# blockDiagram.net
KiCad netlist of a schematic drawn in EAGLE
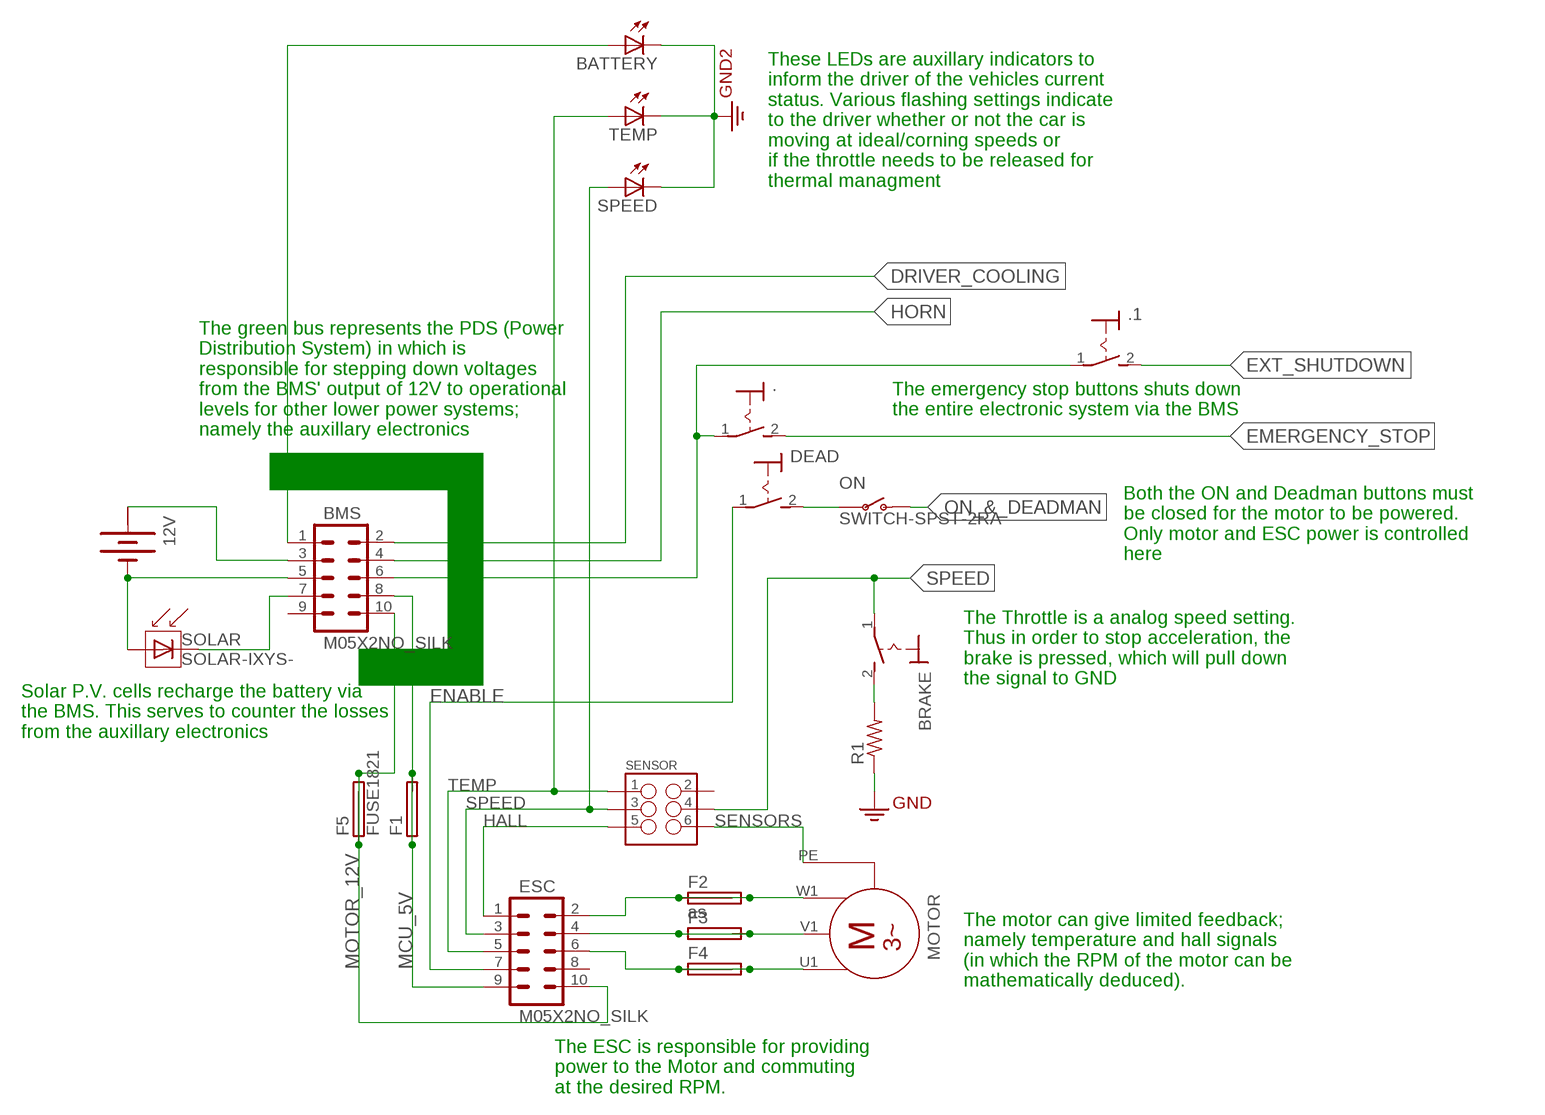
[diagram p0: schematic, sheet 1]

(export (version "E")
  (design (tool "Eeschema 10.0.6"))
  (components
    (comp (ref ".")
      (value "MS243")
      (footprint "eagle-import:MS243")
      (libsource (lib "eagle-import") (part "MS243"))
    )
    (comp (ref ".1")
      (value "MS243")
      (footprint "eagle-import:MS243")
      (libsource (lib "eagle-import") (part "MS243"))
    )
    (comp (ref "12V")
      (value "BATTERY")
      (footprint "eagle-import:BATTERY")
      (libsource (lib "eagle-import") (part "BATTERY"))
    )
    (comp (ref "BATTERY")
      (value "LED1206")
      (footprint "eagle-import:LED-1206")
      (libsource (lib "eagle-import") (part "LED1206"))
    )
    (comp (ref "BMS")
      (value "M05X2NO_SILK")
      (footprint "eagle-import:2X5_NOSILK")
      (libsource (lib "eagle-import") (part "M05X2NO_SILK"))
    )
    (comp (ref "BRAKE")
      (value "MS243")
      (footprint "eagle-import:MS243")
      (libsource (lib "eagle-import") (part "MS243"))
    )
    (comp (ref "DEAD")
      (value "MS243")
      (footprint "eagle-import:MS243")
      (libsource (lib "eagle-import") (part "MS243"))
    )
    (comp (ref "ESC")
      (value "M05X2NO_SILK")
      (footprint "eagle-import:2X5_NOSILK")
      (libsource (lib "eagle-import") (part "M05X2NO_SILK"))
    )
    (comp (ref "F1")
      (value "KS9V")
      (footprint "eagle-import:KS9V")
      (libsource (lib "eagle-import") (part "KS9V"))
    )
    (comp (ref "F2")
      (value "as")
      (footprint "eagle-import:KS9V")
      (libsource (lib "eagle-import") (part "KS9V"))
    )
    (comp (ref "F3")
      (value "KS9V")
      (footprint "eagle-import:KS9V")
      (libsource (lib "eagle-import") (part "KS9V"))
    )
    (comp (ref "F4")
      (value "KS9V")
      (footprint "eagle-import:KS9V")
      (libsource (lib "eagle-import") (part "KS9V"))
    )
    (comp (ref "F5")
      (value "FUSE1821")
      (footprint "eagle-import:FUSE_HOLDER_MENTOR-1821")
      (libsource (lib "eagle-import") (part "FUSE1821"))
    )
    (comp (ref "MOTOR")
      (value "MOTOR_3-POL_PE")
      (footprint "eagle-import:MOTOR_3-POL_PE")
      (libsource (lib "eagle-import") (part "MOTOR_3-POL_PE"))
    )
    (comp (ref "ON")
      (value "SWITCH-SPST-2RA")
      (footprint "eagle-import:R_SW_TH")
      (libsource (lib "eagle-import") (part "SWITCH-SPST-2RA"))
    )
    (comp (ref "R1")
      (value "R-US_0204/2V")
      (footprint "eagle-import:0204V")
      (libsource (lib "eagle-import") (part "R-US_0204/2V"))
    )
    (comp (ref "SENSOR")
      (value "M03X2")
      (footprint "eagle-import:2X3_SMD")
      (libsource (lib "eagle-import") (part "M03X2"))
    )
    (comp (ref "SOLAR")
      (value "SOLAR-IXYS-")
      (footprint "eagle-import:SOLARBIT-12X1")
      (libsource (lib "eagle-import") (part "SOLAR-IXYS-"))
    )
    (comp (ref "SPEED")
      (value "LED1206")
      (footprint "eagle-import:LED-1206")
      (libsource (lib "eagle-import") (part "LED1206"))
    )
    (comp (ref "TEMP")
      (value "LED1206")
      (footprint "eagle-import:LED-1206")
      (libsource (lib "eagle-import") (part "LED1206"))
    )
  )
  (nets
    (net (code "1") (name "/+") (class "Default")
      (node (ref "12V") (pin "+@1") (pinfunction "+_+@1") (pintype "power_in"))
    )
    (net (code "2") (name "/ENABLE") (class "Default")
      (node (ref "DEAD") (pin "1") (pinfunction "P_1") (pintype "passive"))
      (node (ref "ESC") (pin "7") (pinfunction "7_7") (pintype "passive"))
    )
    (net (code "3") (name "/HALL") (class "Default")
      (node (ref "ESC") (pin "1") (pinfunction "1_1") (pintype "passive"))
      (node (ref "SENSOR") (pin "5") (pinfunction "5_5") (pintype "bidirectional"))
    )
    (net (code "4") (name "/MCU_5V") (class "Default")
      (node (ref "BMS") (pin "8") (pinfunction "8_8") (pintype "passive"))
      (node (ref "ESC") (pin "9") (pinfunction "9_9") (pintype "passive"))
      (node (ref "F1") (pin "1") (pinfunction "1_1") (pintype "passive"))
      (node (ref "F1") (pin "2") (pinfunction "2_2") (pintype "passive"))
    )
    (net (code "5") (name "/MOTOR_12V") (class "Default")
      (node (ref "BMS") (pin "10") (pinfunction "10_10") (pintype "passive"))
      (node (ref "ESC") (pin "10") (pinfunction "10_10") (pintype "passive"))
      (node (ref "F5") (pin "A") (pinfunction "1_A") (pintype "passive"))
      (node (ref "F5") (pin "B") (pinfunction "2_B") (pintype "passive"))
    )
    (net (code "6") (name "/SENSORS") (class "Default")
      (node (ref "MOTOR") (pin "PE") (pinfunction "PE_PE") (pintype "passive"))
      (node (ref "SENSOR") (pin "6") (pinfunction "6_6") (pintype "bidirectional"))
    )
    (net (code "7") (name "/TEMP") (class "Default")
      (node (ref "ESC") (pin "5") (pinfunction "5_5") (pintype "passive"))
      (node (ref "SENSOR") (pin "1") (pinfunction "1_1") (pintype "bidirectional"))
      (node (ref "TEMP") (pin "A") (pinfunction "A_A") (pintype "passive"))
    )
    (net (code "8") (name "DRIVER_COOLING") (class "Default")
      (node (ref "BMS") (pin "2") (pinfunction "2_2") (pintype "passive"))
    )
    (net (code "9") (name "EMERGENCY_STOP") (class "Default")
      (node (ref ".") (pin "2") (pinfunction "S_2") (pintype "passive"))
    )
    (net (code "10") (name "EXT_SHUTDOWN") (class "Default")
      (node (ref ".1") (pin "2") (pinfunction "S_2") (pintype "passive"))
    )
    (net (code "11") (name "GND2") (class "Default")
      (node (ref "BATTERY") (pin "C") (pinfunction "C_C") (pintype "passive"))
      (node (ref "R1") (pin "1") (pinfunction "1_1") (pintype "passive"))
      (node (ref "SPEED") (pin "C") (pinfunction "C_C") (pintype "passive"))
      (node (ref "TEMP") (pin "C") (pinfunction "C_C") (pintype "passive"))
    )
    (net (code "12") (name "HORN") (class "Default")
      (node (ref "BMS") (pin "4") (pinfunction "4_4") (pintype "passive"))
    )
    (net (code "13") (name "Net-(.-P)") (class "Default")
      (node (ref ".") (pin "1") (pinfunction "P_1") (pintype "passive"))
      (node (ref ".1") (pin "1") (pinfunction "P_1") (pintype "passive"))
      (node (ref "BMS") (pin "6") (pinfunction "6_6") (pintype "passive"))
    )
    (net (code "14") (name "Net-(12V-Pad+)") (class "Default")
      (node (ref "12V") (pin "+") (pinfunction "+_+") (pintype "power_in"))
      (node (ref "BMS") (pin "3") (pinfunction "3_3") (pintype "passive"))
    )
    (net (code "15") (name "Net-(BATTERY-PadA)") (class "Default")
      (node (ref "BATTERY") (pin "A") (pinfunction "A_A") (pintype "passive"))
      (node (ref "BMS") (pin "1") (pinfunction "1_1") (pintype "passive"))
    )
    (net (code "16") (name "Net-(BRAKE-S)") (class "Default")
      (node (ref "BRAKE") (pin "2") (pinfunction "S_2") (pintype "passive"))
      (node (ref "R1") (pin "2") (pinfunction "2_2") (pintype "passive"))
    )
    (net (code "17") (name "Net-(DEAD-S)") (class "Default")
      (node (ref "DEAD") (pin "2") (pinfunction "S_2") (pintype "passive"))
      (node (ref "ON") (pin "P$4") (pinfunction "P_P$4") (pintype "passive"))
    )
    (net (code "18") (name "Net-(ESC-Pad2)") (class "Default")
      (node (ref "ESC") (pin "2") (pinfunction "2_2") (pintype "passive"))
      (node (ref "F2") (pin "1") (pinfunction "1_1") (pintype "passive"))
      (node (ref "F2") (pin "2") (pinfunction "2_2") (pintype "passive"))
      (node (ref "MOTOR") (pin "W1") (pinfunction "W1_W1") (pintype "passive"))
    )
    (net (code "19") (name "Net-(ESC-Pad4)") (class "Default")
      (node (ref "ESC") (pin "4") (pinfunction "4_4") (pintype "passive"))
      (node (ref "F3") (pin "1") (pinfunction "1_1") (pintype "passive"))
      (node (ref "F3") (pin "2") (pinfunction "2_2") (pintype "passive"))
      (node (ref "MOTOR") (pin "V1") (pinfunction "V1_V1") (pintype "passive"))
    )
    (net (code "20") (name "Net-(ESC-Pad6)") (class "Default")
      (node (ref "ESC") (pin "6") (pinfunction "6_6") (pintype "passive"))
      (node (ref "F4") (pin "1") (pinfunction "1_1") (pintype "passive"))
      (node (ref "F4") (pin "2") (pinfunction "2_2") (pintype "passive"))
      (node (ref "MOTOR") (pin "U1") (pinfunction "U1_U1") (pintype "passive"))
    )
    (net (code "21") (name "Net-(SOLAR-A)") (class "Default")
      (node (ref "12V") (pin "-") (pinfunction "-_-") (pintype "power_in"))
      (node (ref "BMS") (pin "5") (pinfunction "5_5") (pintype "passive"))
      (node (ref "SOLAR") (pin "+") (pinfunction "A_+") (pintype "passive"))
    )
    (net (code "22") (name "Net-(SOLAR-C)") (class "Default")
      (node (ref "BMS") (pin "7") (pinfunction "7_7") (pintype "passive"))
      (node (ref "SOLAR") (pin "-") (pinfunction "C_-") (pintype "passive"))
    )
    (net (code "23") (name "ON_&_DEADMAN") (class "Default")
      (node (ref "ON") (pin "P$3") (pinfunction "O_P$3") (pintype "passive"))
    )
    (net (code "24") (name "SPEED") (class "Default")
      (node (ref "BRAKE") (pin "1") (pinfunction "P_1") (pintype "passive"))
      (node (ref "ESC") (pin "3") (pinfunction "3_3") (pintype "passive"))
      (node (ref "SENSOR") (pin "3") (pinfunction "3_3") (pintype "bidirectional"))
      (node (ref "SENSOR") (pin "4") (pinfunction "4_4") (pintype "bidirectional"))
      (node (ref "SPEED") (pin "A") (pinfunction "A_A") (pintype "passive"))
    )
    (net (code "25") (name "unconnected-(BMS-Pad9)") (class "Default")
      (node (ref "BMS") (pin "9") (pinfunction "9_9") (pintype "passive"))
    )
    (net (code "26") (name "unconnected-(ESC-Pad8)") (class "Default")
      (node (ref "ESC") (pin "8") (pinfunction "8_8") (pintype "passive"))
    )
    (net (code "27") (name "unconnected-(SENSOR-Pad2)") (class "Default")
      (node (ref "SENSOR") (pin "2") (pinfunction "2_2") (pintype "bidirectional"))
    )
  )
)
